# business_card_serial_temp.net
KiCad netlist of a schematic drawn in EAGLE
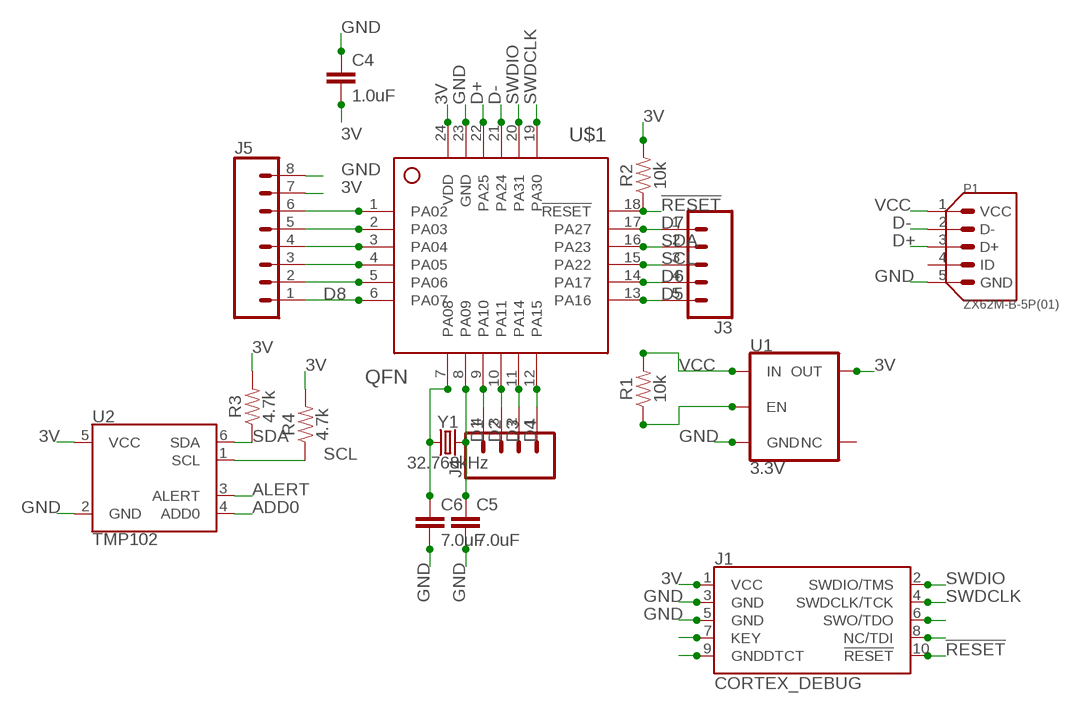
[diagram p0: schematic, sheet 1]

(export (version "E")
  (design (tool "Eeschema 10.0.6"))
  (components
    (comp (ref "C4")
      (value "1.0uF")
      (footprint "eagle-import:0402")
      (libsource (lib "eagle-import") (part "1.0UF-0402-16V-10%"))
    )
    (comp (ref "C5")
      (value "7.0uF")
      (footprint "eagle-import:0402")
      (libsource (lib "eagle-import") (part "1.0UF-0402-16V-10%"))
    )
    (comp (ref "C6")
      (value "7.0uF")
      (footprint "eagle-import:0402")
      (libsource (lib "eagle-import") (part "1.0UF-0402-16V-10%"))
    )
    (comp (ref "J1")
      (value "CORTEX_DEBUG")
      (footprint "eagle-import:2X5-PTH-1.27MM")
      (libsource (lib "eagle-import") (part "CORTEX_DEBUG_PTH"))
    )
    (comp (ref "J3")
      (value "CONN_05")
      (footprint "eagle-import:1X05")
      (libsource (lib "eagle-import") (part "CONN_05"))
    )
    (comp (ref "J4")
      (value "CONN_04")
      (footprint "eagle-import:1X04")
      (libsource (lib "eagle-import") (part "CONN_04"))
    )
    (comp (ref "J5")
      (value "CONN_08\"")
      (footprint "eagle-import:1X08")
      (libsource (lib "eagle-import") (part "CONN_08{dblquote}"))
    )
    (comp (ref "P1")
      (value "ZX62M-B-5P(01)")
      (footprint "eagle-import:HRS_ZX62M-B-5P(01)")
      (fields (field (name "MF") "Hirose") (field (name "MP") "ZX62M-B-5P_01_"))
      (libsource (lib "eagle-import") (part "ZX62M-B-5P(01)"))
    )
    (comp (ref "R1")
      (value "10k")
      (footprint "eagle-import:0603")
      (libsource (lib "eagle-import") (part "330OHM-0603-1/10W-1%"))
    )
    (comp (ref "R2")
      (value "10k")
      (footprint "eagle-import:0603")
      (libsource (lib "eagle-import") (part "330OHM-0603-1/10W-1%"))
    )
    (comp (ref "R3")
      (value "4.7k")
      (footprint "eagle-import:0603")
      (libsource (lib "eagle-import") (part "330OHM-0603-1/10W-1%"))
    )
    (comp (ref "R4")
      (value "4.7k")
      (footprint "eagle-import:0603")
      (libsource (lib "eagle-import") (part "330OHM-0603-1/10W-1%"))
    )
    (comp (ref "U$1")
      (value "QFN")
      (footprint "eagle-import:QFN24-4X4")
      (libsource (lib "eagle-import") (part "QFN"))
    )
    (comp (ref "U1")
      (value "3.3V")
      (footprint "eagle-import:SOT23-5")
      (libsource (lib "eagle-import") (part "V_REG_AP2112K-3.3V"))
    )
    (comp (ref "U2")
      (value "TMP102")
      (footprint "eagle-import:SOT563")
      (fields (field (name "MF") "Texas Instruments"))
      (libsource (lib "eagle-import") (part "TMP102"))
    )
    (comp (ref "Y1")
      (value "32.768kHz")
      (footprint "eagle-import:CRYSTAL-SMD-3.2X1.5MM")
      (libsource (lib "eagle-import") (part "CRYSTAL-32.768KHZSMD-3.2X1.5"))
    )
  )
  (nets
    (net (code "1") (name "/3V") (class "Default")
      (node (ref "C4") (pin "2") (pinfunction "2_2") (pintype "passive"))
      (node (ref "J1") (pin "1") (pinfunction "VCC_1") (pintype "bidirectional"))
      (node (ref "J5") (pin "7") (pinfunction "7_7") (pintype "passive"))
      (node (ref "R2") (pin "2") (pinfunction "2_2") (pintype "passive"))
      (node (ref "R3") (pin "2") (pinfunction "2_2") (pintype "passive"))
      (node (ref "R4") (pin "2") (pinfunction "2_2") (pintype "passive"))
      (node (ref "U$1") (pin "24") (pinfunction "VDD_24") (pintype "bidirectional"))
      (node (ref "U1") (pin "5") (pinfunction "OUT_5") (pintype "passive"))
      (node (ref "U2") (pin "5") (pinfunction "VCC_5") (pintype "bidirectional"))
    )
    (net (code "2") (name "/ADD0") (class "Default")
      (node (ref "U2") (pin "4") (pinfunction "ADD0_4") (pintype "bidirectional"))
    )
    (net (code "3") (name "/ALERT") (class "Default")
      (node (ref "U2") (pin "3") (pinfunction "ALERT_3") (pintype "bidirectional"))
    )
    (net (code "4") (name "/D+") (class "Default")
      (node (ref "P1") (pin "3") (pinfunction "D+_3") (pintype "bidirectional"))
      (node (ref "U$1") (pin "22") (pinfunction "PA25_22") (pintype "bidirectional"))
    )
    (net (code "5") (name "/D-") (class "Default")
      (node (ref "P1") (pin "2") (pinfunction "D-_2") (pintype "bidirectional"))
      (node (ref "U$1") (pin "21") (pinfunction "PA24_21") (pintype "bidirectional"))
    )
    (net (code "6") (name "/D1") (class "Default")
      (node (ref "J4") (pin "4") (pinfunction "4_4") (pintype "passive"))
      (node (ref "U$1") (pin "9") (pinfunction "PA10_9") (pintype "bidirectional"))
    )
    (net (code "7") (name "/D2") (class "Default")
      (node (ref "J4") (pin "3") (pinfunction "3_3") (pintype "passive"))
      (node (ref "U$1") (pin "10") (pinfunction "PA11_10") (pintype "bidirectional"))
    )
    (net (code "8") (name "/D3") (class "Default")
      (node (ref "J4") (pin "2") (pinfunction "2_2") (pintype "passive"))
      (node (ref "U$1") (pin "11") (pinfunction "PA14_11") (pintype "bidirectional"))
    )
    (net (code "9") (name "/D4") (class "Default")
      (node (ref "J4") (pin "1") (pinfunction "1_1") (pintype "passive"))
      (node (ref "U$1") (pin "12") (pinfunction "PA15_12") (pintype "bidirectional"))
    )
    (net (code "10") (name "/D5") (class "Default")
      (node (ref "J3") (pin "5") (pinfunction "5_5") (pintype "passive"))
      (node (ref "U$1") (pin "13") (pinfunction "PA16_13") (pintype "bidirectional"))
    )
    (net (code "11") (name "/D6") (class "Default")
      (node (ref "J3") (pin "4") (pinfunction "4_4") (pintype "passive"))
      (node (ref "U$1") (pin "14") (pinfunction "PA17_14") (pintype "bidirectional"))
    )
    (net (code "12") (name "/D7") (class "Default")
      (node (ref "J3") (pin "1") (pinfunction "1_1") (pintype "passive"))
      (node (ref "U$1") (pin "17") (pinfunction "PA27_17") (pintype "bidirectional"))
    )
    (net (code "13") (name "/D8") (class "Default")
      (node (ref "J5") (pin "1") (pinfunction "1_1") (pintype "passive"))
      (node (ref "U$1") (pin "6") (pinfunction "PA07_6") (pintype "bidirectional"))
    )
    (net (code "14") (name "/GND") (class "Default")
      (node (ref "C4") (pin "1") (pinfunction "1_1") (pintype "passive"))
      (node (ref "C5") (pin "2") (pinfunction "2_2") (pintype "passive"))
      (node (ref "C6") (pin "2") (pinfunction "2_2") (pintype "passive"))
      (node (ref "J1") (pin "3") (pinfunction "GND_3") (pintype "bidirectional"))
      (node (ref "J1") (pin "5") (pinfunction "GND_5") (pintype "bidirectional"))
      (node (ref "J5") (pin "8") (pinfunction "8_8") (pintype "passive"))
      (node (ref "P1") (pin "5") (pinfunction "GND_5") (pintype "passive"))
      (node (ref "U$1") (pin "23") (pinfunction "GND_23") (pintype "bidirectional"))
      (node (ref "U1") (pin "2") (pinfunction "GND_2") (pintype "input"))
      (node (ref "U2") (pin "2") (pinfunction "GND_2") (pintype "bidirectional"))
    )
    (net (code "15") (name "/SCL") (class "Default")
      (node (ref "J3") (pin "3") (pinfunction "3_3") (pintype "passive"))
      (node (ref "R4") (pin "1") (pinfunction "1_1") (pintype "passive"))
      (node (ref "U$1") (pin "15") (pinfunction "PA22_15") (pintype "bidirectional"))
      (node (ref "U2") (pin "1") (pinfunction "SCL_1") (pintype "bidirectional"))
    )
    (net (code "16") (name "/SDA") (class "Default")
      (node (ref "J3") (pin "2") (pinfunction "2_2") (pintype "passive"))
      (node (ref "R3") (pin "1") (pinfunction "1_1") (pintype "passive"))
      (node (ref "U$1") (pin "16") (pinfunction "PA23_16") (pintype "bidirectional"))
      (node (ref "U2") (pin "6") (pinfunction "SDA_6") (pintype "bidirectional"))
    )
    (net (code "17") (name "/SWDCLK") (class "Default")
      (node (ref "J1") (pin "4") (pinfunction "SWDCLK/TCK_4") (pintype "bidirectional"))
      (node (ref "U$1") (pin "19") (pinfunction "PA30_19") (pintype "bidirectional"))
    )
    (net (code "18") (name "/SWDIO") (class "Default")
      (node (ref "J1") (pin "2") (pinfunction "SWDIO/TMS_2") (pintype "bidirectional"))
      (node (ref "U$1") (pin "20") (pinfunction "PA31_20") (pintype "bidirectional"))
    )
    (net (code "19") (name "/VCC") (class "Default")
      (node (ref "P1") (pin "1") (pinfunction "VCC_1") (pintype "power_in"))
      (node (ref "R1") (pin "2") (pinfunction "2_2") (pintype "passive"))
      (node (ref "U1") (pin "1") (pinfunction "IN_1") (pintype "input"))
    )
    (net (code "20") (name "/~{RESET}") (class "Default")
      (node (ref "J1") (pin "10") (pinfunction "~{RESET}_10") (pintype "bidirectional"))
      (node (ref "R2") (pin "1") (pinfunction "1_1") (pintype "passive"))
      (node (ref "U$1") (pin "18") (pinfunction "~{RESET}_18") (pintype "bidirectional"))
    )
    (net (code "21") (name "Net-(U$1-PA02)") (class "Default")
      (node (ref "J5") (pin "6") (pinfunction "6_6") (pintype "passive"))
      (node (ref "U$1") (pin "1") (pinfunction "PA02_1") (pintype "bidirectional"))
    )
    (net (code "22") (name "Net-(U$1-PA03)") (class "Default")
      (node (ref "J5") (pin "5") (pinfunction "5_5") (pintype "passive"))
      (node (ref "U$1") (pin "2") (pinfunction "PA03_2") (pintype "bidirectional"))
    )
    (net (code "23") (name "Net-(U$1-PA04)") (class "Default")
      (node (ref "J5") (pin "4") (pinfunction "4_4") (pintype "passive"))
      (node (ref "U$1") (pin "3") (pinfunction "PA04_3") (pintype "bidirectional"))
    )
    (net (code "24") (name "Net-(U$1-PA05)") (class "Default")
      (node (ref "J5") (pin "3") (pinfunction "3_3") (pintype "passive"))
      (node (ref "U$1") (pin "4") (pinfunction "PA05_4") (pintype "bidirectional"))
    )
    (net (code "25") (name "Net-(U$1-PA06)") (class "Default")
      (node (ref "J5") (pin "2") (pinfunction "2_2") (pintype "passive"))
      (node (ref "U$1") (pin "5") (pinfunction "PA06_5") (pintype "bidirectional"))
    )
    (net (code "26") (name "Net-(U$1-PA08)") (class "Default")
      (node (ref "C6") (pin "1") (pinfunction "1_1") (pintype "passive"))
      (node (ref "U$1") (pin "7") (pinfunction "PA08_7") (pintype "bidirectional"))
      (node (ref "Y1") (pin "P$1") (pinfunction "1_P$1") (pintype "passive"))
    )
    (net (code "27") (name "Net-(U$1-PA09)") (class "Default")
      (node (ref "C5") (pin "1") (pinfunction "1_1") (pintype "passive"))
      (node (ref "U$1") (pin "8") (pinfunction "PA09_8") (pintype "bidirectional"))
      (node (ref "Y1") (pin "P$2") (pinfunction "2_P$2") (pintype "passive"))
    )
    (net (code "28") (name "Net-(U1-EN)") (class "Default")
      (node (ref "R1") (pin "1") (pinfunction "1_1") (pintype "passive"))
      (node (ref "U1") (pin "3") (pinfunction "EN_3") (pintype "input"))
    )
    (net (code "29") (name "unconnected-(J1-GNDDTCT-Pad9)") (class "Default")
      (node (ref "J1") (pin "9") (pinfunction "GNDDTCT_9") (pintype "bidirectional"))
    )
    (net (code "30") (name "unconnected-(J1-KEY-Pad7)") (class "Default")
      (node (ref "J1") (pin "7") (pinfunction "KEY_7") (pintype "bidirectional"))
    )
    (net (code "31") (name "unconnected-(J1-NC{slash}TDI-Pad8)") (class "Default")
      (node (ref "J1") (pin "8") (pinfunction "NC/TDI_8") (pintype "bidirectional"))
    )
    (net (code "32") (name "unconnected-(J1-SWO{slash}TDO-Pad6)") (class "Default")
      (node (ref "J1") (pin "6") (pinfunction "SWO/TDO_6") (pintype "bidirectional"))
    )
    (net (code "33") (name "unconnected-(P1-ID-Pad4)") (class "Default")
      (node (ref "P1") (pin "4") (pinfunction "ID_4") (pintype "bidirectional"))
    )
    (net (code "34") (name "unconnected-(U1-NC-Pad4)") (class "Default")
      (node (ref "U1") (pin "4") (pinfunction "NC_4") (pintype "no_connect"))
    )
  )
)
